# balancewheel.net
KiCad netlist of a schematic drawn in EAGLE
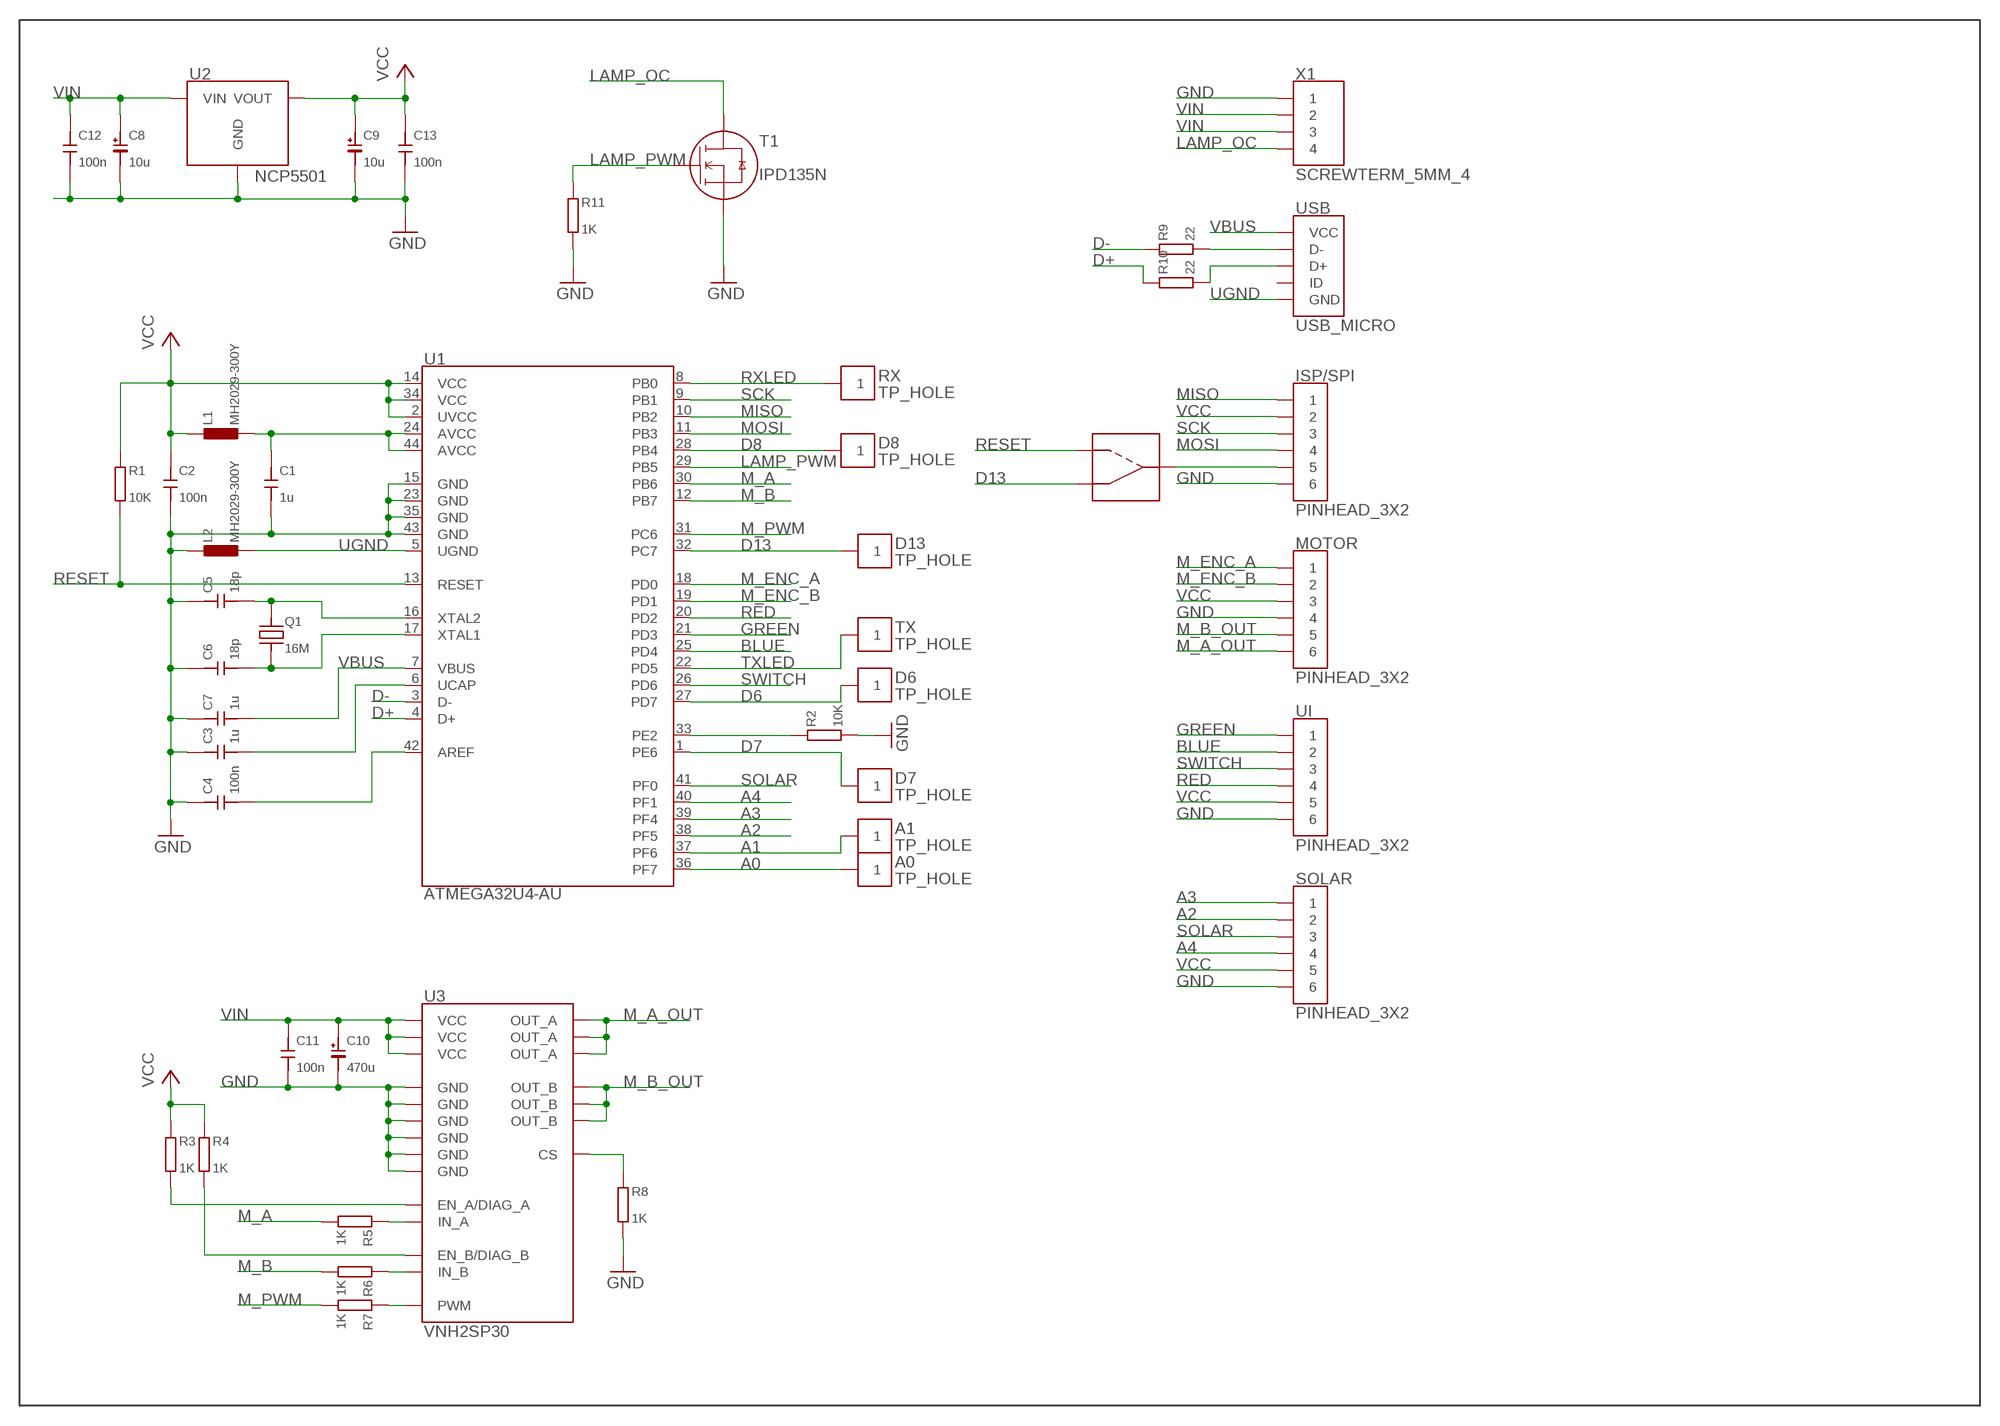
[diagram p0: schematic, sheet 1]

(export (version "E")
  (design (tool "Eeschema 10.0.6"))
  (components
    (comp (ref "A0")
      (value "TP_HOLE")
      (footprint "eagle-import:X1")
      (libsource (lib "eagle-import") (part "TP_HOLE"))
    )
    (comp (ref "A1")
      (value "TP_HOLE")
      (footprint "eagle-import:X1")
      (libsource (lib "eagle-import") (part "TP_HOLE"))
    )
    (comp (ref "C1")
      (value "1u")
      (footprint "eagle-import:0805")
      (libsource (lib "eagle-import") (part "C0805"))
    )
    (comp (ref "C2")
      (value "100n")
      (footprint "eagle-import:0805")
      (libsource (lib "eagle-import") (part "C0805"))
    )
    (comp (ref "C3")
      (value "1u")
      (footprint "eagle-import:0805")
      (libsource (lib "eagle-import") (part "C0805"))
    )
    (comp (ref "C4")
      (value "100n")
      (footprint "eagle-import:0805")
      (libsource (lib "eagle-import") (part "C0805"))
    )
    (comp (ref "C5")
      (value "18p")
      (footprint "eagle-import:0805")
      (libsource (lib "eagle-import") (part "C0805"))
    )
    (comp (ref "C6")
      (value "18p")
      (footprint "eagle-import:0805")
      (libsource (lib "eagle-import") (part "C0805"))
    )
    (comp (ref "C7")
      (value "1u")
      (footprint "eagle-import:0805")
      (libsource (lib "eagle-import") (part "C0805"))
    )
    (comp (ref "C8")
      (value "10u")
      (footprint "eagle-import:CPOL_C")
      (libsource (lib "eagle-import") (part "CPOL_C"))
    )
    (comp (ref "C9")
      (value "10u")
      (footprint "eagle-import:CPOL_C")
      (libsource (lib "eagle-import") (part "CPOL_C"))
    )
    (comp (ref "C10")
      (value "470u")
      (footprint "eagle-import:CPOL_10")
      (libsource (lib "eagle-import") (part "CPOL_10"))
    )
    (comp (ref "C11")
      (value "100n")
      (footprint "eagle-import:0805")
      (libsource (lib "eagle-import") (part "C0805"))
    )
    (comp (ref "C12")
      (value "100n")
      (footprint "eagle-import:0805")
      (libsource (lib "eagle-import") (part "C0805"))
    )
    (comp (ref "C13")
      (value "100n")
      (footprint "eagle-import:0805")
      (libsource (lib "eagle-import") (part "C0805"))
    )
    (comp (ref "D6")
      (value "TP_HOLE")
      (footprint "eagle-import:X1")
      (libsource (lib "eagle-import") (part "TP_HOLE"))
    )
    (comp (ref "D7")
      (value "TP_HOLE")
      (footprint "eagle-import:X1")
      (libsource (lib "eagle-import") (part "TP_HOLE"))
    )
    (comp (ref "D8")
      (value "TP_HOLE")
      (footprint "eagle-import:X1")
      (libsource (lib "eagle-import") (part "TP_HOLE"))
    )
    (comp (ref "D13")
      (value "TP_HOLE")
      (footprint "eagle-import:X1")
      (libsource (lib "eagle-import") (part "TP_HOLE"))
    )
    (comp (ref "ISP/SPI")
      (value "PINHEAD_3X2")
      (footprint "eagle-import:3X2")
      (libsource (lib "eagle-import") (part "PINHEAD_3X2"))
    )
    (comp (ref "L1")
      (value "MH2029-300Y")
      (footprint "eagle-import:0805")
      (libsource (lib "eagle-import") (part "L0805"))
    )
    (comp (ref "L2")
      (value "MH2029-300Y")
      (footprint "eagle-import:0805")
      (libsource (lib "eagle-import") (part "L0805"))
    )
    (comp (ref "MOTOR")
      (value "PINHEAD_3X2")
      (footprint "eagle-import:3X2")
      (libsource (lib "eagle-import") (part "PINHEAD_3X2"))
    )
    (comp (ref "Q1")
      (value "16M")
      (footprint "eagle-import:Q5X32")
      (libsource (lib "eagle-import") (part "Q5X32"))
    )
    (comp (ref "R1")
      (value "10K")
      (footprint "eagle-import:0805")
      (libsource (lib "eagle-import") (part "R0805"))
    )
    (comp (ref "R2")
      (value "10K")
      (footprint "eagle-import:0805")
      (libsource (lib "eagle-import") (part "R0805"))
    )
    (comp (ref "R3")
      (value "1K")
      (footprint "eagle-import:0805")
      (libsource (lib "eagle-import") (part "R0805"))
    )
    (comp (ref "R4")
      (value "1K")
      (footprint "eagle-import:0805")
      (libsource (lib "eagle-import") (part "R0805"))
    )
    (comp (ref "R5")
      (value "1K")
      (footprint "eagle-import:0805")
      (libsource (lib "eagle-import") (part "R0805"))
    )
    (comp (ref "R6")
      (value "1K")
      (footprint "eagle-import:0805")
      (libsource (lib "eagle-import") (part "R0805"))
    )
    (comp (ref "R7")
      (value "1K")
      (footprint "eagle-import:0805")
      (libsource (lib "eagle-import") (part "R0805"))
    )
    (comp (ref "R8")
      (value "1K")
      (footprint "eagle-import:0805")
      (libsource (lib "eagle-import") (part "R0805"))
    )
    (comp (ref "R9")
      (value "22")
      (footprint "eagle-import:0805")
      (libsource (lib "eagle-import") (part "R0805"))
    )
    (comp (ref "R10")
      (value "22")
      (footprint "eagle-import:0805")
      (libsource (lib "eagle-import") (part "R0805"))
    )
    (comp (ref "R11")
      (value "1K")
      (footprint "eagle-import:0805")
      (libsource (lib "eagle-import") (part "R0805"))
    )
    (comp (ref "RX")
      (value "TP_HOLE")
      (footprint "eagle-import:X1")
      (libsource (lib "eagle-import") (part "TP_HOLE"))
    )
    (comp (ref "SJ1") (value "SJ") (footprint "eagle-import:X3") (libsource (lib "eagle-import") (part "SJ")))
    (comp (ref "SOLAR")
      (value "PINHEAD_3X2")
      (footprint "eagle-import:3X2")
      (libsource (lib "eagle-import") (part "PINHEAD_3X2"))
    )
    (comp (ref "T1")
      (value "IPD135N")
      (footprint "eagle-import:DPAK")
      (libsource (lib "eagle-import") (part "MOSFET_N_DPAK"))
    )
    (comp (ref "TX")
      (value "TP_HOLE")
      (footprint "eagle-import:X1")
      (libsource (lib "eagle-import") (part "TP_HOLE"))
    )
    (comp (ref "U1")
      (value "ATMEGA32U4-AU")
      (footprint "eagle-import:TQFP44")
      (libsource (lib "eagle-import") (part "ATMEGA32U4-AU"))
    )
    (comp (ref "U2")
      (value "NCP5501")
      (footprint "eagle-import:DPAK")
      (libsource (lib "eagle-import") (part "NCP5501"))
    )
    (comp (ref "U3")
      (value "VNH2SP30")
      (footprint "eagle-import:MULTIPOWER30")
      (libsource (lib "eagle-import") (part "VNH2SP30"))
    )
    (comp (ref "UI")
      (value "PINHEAD_3X2")
      (footprint "eagle-import:3X2")
      (libsource (lib "eagle-import") (part "PINHEAD_3X2"))
    )
    (comp (ref "USB")
      (value "USB_MICRO")
      (footprint "eagle-import:MUSB")
      (libsource (lib "eagle-import") (part "USB_MICRO"))
    )
    (comp (ref "X1")
      (value "SCREWTERM_5MM_4")
      (footprint "eagle-import:5MMSCREWTERMX4")
      (libsource (lib "eagle-import") (part "SCREWTERM_5MM_4"))
    )
  )
  (nets
    (net (code "1") (name "/A0") (class "Default")
      (node (ref "A0") (pin "P$1") (pinfunction "1_P$1") (pintype "bidirectional"))
      (node (ref "U1") (pin "36") (pinfunction "PF7_36") (pintype "bidirectional"))
    )
    (net (code "2") (name "/A1") (class "Default")
      (node (ref "A1") (pin "P$1") (pinfunction "1_P$1") (pintype "bidirectional"))
      (node (ref "U1") (pin "37") (pinfunction "PF6_37") (pintype "bidirectional"))
    )
    (net (code "3") (name "/A2") (class "Default")
      (node (ref "SOLAR") (pin "2") (pinfunction "2_2") (pintype "bidirectional"))
      (node (ref "U1") (pin "38") (pinfunction "PF5_38") (pintype "bidirectional"))
    )
    (net (code "4") (name "/A3") (class "Default")
      (node (ref "SOLAR") (pin "1") (pinfunction "1_1") (pintype "bidirectional"))
      (node (ref "U1") (pin "39") (pinfunction "PF4_39") (pintype "bidirectional"))
    )
    (net (code "5") (name "/A4") (class "Default")
      (node (ref "SOLAR") (pin "4") (pinfunction "4_4") (pintype "bidirectional"))
      (node (ref "U1") (pin "40") (pinfunction "PF1_40") (pintype "bidirectional"))
    )
    (net (code "6") (name "/BLUE") (class "Default")
      (node (ref "U1") (pin "25") (pinfunction "PD4_25") (pintype "bidirectional"))
      (node (ref "UI") (pin "2") (pinfunction "2_2") (pintype "bidirectional"))
    )
    (net (code "7") (name "/D+") (class "Default")
      (node (ref "R10") (pin "P$2") (pinfunction "P$2_P$2") (pintype "bidirectional"))
      (node (ref "U1") (pin "4") (pinfunction "D+_4") (pintype "bidirectional"))
    )
    (net (code "8") (name "/D-") (class "Default")
      (node (ref "R9") (pin "P$2") (pinfunction "P$2_P$2") (pintype "bidirectional"))
      (node (ref "U1") (pin "3") (pinfunction "D-_3") (pintype "bidirectional"))
    )
    (net (code "9") (name "/D6") (class "Default")
      (node (ref "D6") (pin "P$1") (pinfunction "1_P$1") (pintype "bidirectional"))
      (node (ref "U1") (pin "27") (pinfunction "PD7_27") (pintype "bidirectional"))
    )
    (net (code "10") (name "/D7") (class "Default")
      (node (ref "D7") (pin "P$1") (pinfunction "1_P$1") (pintype "bidirectional"))
      (node (ref "U1") (pin "1") (pinfunction "PE6_1") (pintype "bidirectional"))
    )
    (net (code "11") (name "/D8") (class "Default")
      (node (ref "D8") (pin "P$1") (pinfunction "1_P$1") (pintype "bidirectional"))
      (node (ref "U1") (pin "28") (pinfunction "PB4_28") (pintype "bidirectional"))
    )
    (net (code "12") (name "/D13") (class "Default")
      (node (ref "D13") (pin "P$1") (pinfunction "1_P$1") (pintype "bidirectional"))
      (node (ref "SJ1") (pin "1") (pinfunction "1_1") (pintype "bidirectional"))
      (node (ref "U1") (pin "32") (pinfunction "PC7_32") (pintype "bidirectional"))
    )
    (net (code "13") (name "/GREEN") (class "Default")
      (node (ref "U1") (pin "21") (pinfunction "PD3_21") (pintype "bidirectional"))
      (node (ref "UI") (pin "1") (pinfunction "1_1") (pintype "bidirectional"))
    )
    (net (code "14") (name "/LAMP_OC") (class "Default")
      (node (ref "T1") (pin "TAB") (pinfunction "D_TAB") (pintype "bidirectional"))
      (node (ref "X1") (pin "4") (pinfunction "4_4") (pintype "bidirectional"))
    )
    (net (code "15") (name "/LAMP_PWM") (class "Default")
      (node (ref "R11") (pin "P$2") (pinfunction "P$2_P$2") (pintype "bidirectional"))
      (node (ref "T1") (pin "1") (pinfunction "G_1") (pintype "bidirectional"))
      (node (ref "U1") (pin "29") (pinfunction "PB5_29") (pintype "bidirectional"))
    )
    (net (code "16") (name "/MISO") (class "Default")
      (node (ref "ISP/SPI") (pin "1") (pinfunction "1_1") (pintype "bidirectional"))
      (node (ref "U1") (pin "10") (pinfunction "PB2_10") (pintype "bidirectional"))
    )
    (net (code "17") (name "/MOSI") (class "Default")
      (node (ref "ISP/SPI") (pin "4") (pinfunction "4_4") (pintype "bidirectional"))
      (node (ref "U1") (pin "11") (pinfunction "PB3_11") (pintype "bidirectional"))
    )
    (net (code "18") (name "/M_A") (class "Default")
      (node (ref "R5") (pin "P$1") (pinfunction "P$1_P$1") (pintype "bidirectional"))
      (node (ref "U1") (pin "30") (pinfunction "PB6_30") (pintype "bidirectional"))
    )
    (net (code "19") (name "/M_A_OUT") (class "Default")
      (node (ref "MOTOR") (pin "6") (pinfunction "6_6") (pintype "bidirectional"))
      (node (ref "U3") (pin "P$1") (pinfunction "OUT_A_P$1") (pintype "output"))
      (node (ref "U3") (pin "P$25") (pinfunction "OUT_A_P$25") (pintype "output"))
      (node (ref "U3") (pin "P$30") (pinfunction "OUT_A_P$30") (pintype "output"))
    )
    (net (code "20") (name "/M_B") (class "Default")
      (node (ref "R6") (pin "P$1") (pinfunction "P$1_P$1") (pintype "bidirectional"))
      (node (ref "U1") (pin "12") (pinfunction "PB7_12") (pintype "bidirectional"))
    )
    (net (code "21") (name "/M_B_OUT") (class "Default")
      (node (ref "MOTOR") (pin "5") (pinfunction "5_5") (pintype "bidirectional"))
      (node (ref "U3") (pin "P$15") (pinfunction "OUT_B_P$15") (pintype "output"))
      (node (ref "U3") (pin "P$16") (pinfunction "OUT_B_P$16") (pintype "output"))
      (node (ref "U3") (pin "P$21") (pinfunction "OUT_B_P$21") (pintype "output"))
    )
    (net (code "22") (name "/M_ENC_A") (class "Default")
      (node (ref "MOTOR") (pin "1") (pinfunction "1_1") (pintype "bidirectional"))
      (node (ref "U1") (pin "18") (pinfunction "PD0_18") (pintype "bidirectional"))
    )
    (net (code "23") (name "/M_ENC_B") (class "Default")
      (node (ref "MOTOR") (pin "2") (pinfunction "2_2") (pintype "bidirectional"))
      (node (ref "U1") (pin "19") (pinfunction "PD1_19") (pintype "bidirectional"))
    )
    (net (code "24") (name "/M_PWM") (class "Default")
      (node (ref "R7") (pin "P$1") (pinfunction "P$1_P$1") (pintype "bidirectional"))
      (node (ref "U1") (pin "31") (pinfunction "PC6_31") (pintype "bidirectional"))
    )
    (net (code "25") (name "/RED") (class "Default")
      (node (ref "U1") (pin "20") (pinfunction "PD2_20") (pintype "bidirectional"))
      (node (ref "UI") (pin "4") (pinfunction "4_4") (pintype "bidirectional"))
    )
    (net (code "26") (name "/RESET") (class "Default")
      (node (ref "R1") (pin "P$1") (pinfunction "P$1_P$1") (pintype "bidirectional"))
      (node (ref "SJ1") (pin "3") (pinfunction "3_3") (pintype "bidirectional"))
      (node (ref "U1") (pin "13") (pinfunction "RESET_13") (pintype "bidirectional"))
    )
    (net (code "27") (name "/RXLED") (class "Default")
      (node (ref "RX") (pin "P$1") (pinfunction "1_P$1") (pintype "bidirectional"))
      (node (ref "U1") (pin "8") (pinfunction "PB0_8") (pintype "bidirectional"))
    )
    (net (code "28") (name "/SCK") (class "Default")
      (node (ref "ISP/SPI") (pin "3") (pinfunction "3_3") (pintype "bidirectional"))
      (node (ref "U1") (pin "9") (pinfunction "PB1_9") (pintype "bidirectional"))
    )
    (net (code "29") (name "/SOLAR") (class "Default")
      (node (ref "SOLAR") (pin "3") (pinfunction "3_3") (pintype "bidirectional"))
      (node (ref "U1") (pin "41") (pinfunction "PF0_41") (pintype "bidirectional"))
    )
    (net (code "30") (name "/SWITCH") (class "Default")
      (node (ref "U1") (pin "26") (pinfunction "PD6_26") (pintype "bidirectional"))
      (node (ref "UI") (pin "3") (pinfunction "3_3") (pintype "bidirectional"))
    )
    (net (code "31") (name "/TXLED") (class "Default")
      (node (ref "TX") (pin "P$1") (pinfunction "1_P$1") (pintype "bidirectional"))
      (node (ref "U1") (pin "22") (pinfunction "PD5_22") (pintype "bidirectional"))
    )
    (net (code "32") (name "/UGND") (class "Default")
      (node (ref "L2") (pin "P$1") (pinfunction "P$1_P$1") (pintype "bidirectional"))
      (node (ref "U1") (pin "5") (pinfunction "UGND_5") (pintype "power_in"))
      (node (ref "USB") (pin "5") (pinfunction "GND_5") (pintype "bidirectional"))
    )
    (net (code "33") (name "/VBUS") (class "Default")
      (node (ref "C7") (pin "P$1") (pinfunction "P$1_P$1") (pintype "bidirectional"))
      (node (ref "U1") (pin "7") (pinfunction "VBUS_7") (pintype "bidirectional"))
      (node (ref "USB") (pin "1") (pinfunction "VCC_1") (pintype "bidirectional"))
    )
    (net (code "34") (name "/VIN") (class "Default")
      (node (ref "C10") (pin "POS") (pinfunction "POS_POS") (pintype "bidirectional"))
      (node (ref "C11") (pin "P$2") (pinfunction "P$2_P$2") (pintype "bidirectional"))
      (node (ref "C12") (pin "P$2") (pinfunction "P$2_P$2") (pintype "bidirectional"))
      (node (ref "C8") (pin "POS") (pinfunction "POS_POS") (pintype "bidirectional"))
      (node (ref "U2") (pin "1") (pinfunction "VIN_1") (pintype "power_in"))
      (node (ref "U3") (pin "P$13") (pinfunction "VCC_P$13") (pintype "power_in"))
      (node (ref "U3") (pin "P$23") (pinfunction "VCC_P$23") (pintype "power_in"))
      (node (ref "U3") (pin "P$3") (pinfunction "VCC_P$3") (pintype "power_in"))
      (node (ref "X1") (pin "2") (pinfunction "2_2") (pintype "bidirectional"))
      (node (ref "X1") (pin "3") (pinfunction "3_3") (pintype "bidirectional"))
    )
    (net (code "35") (name "GND") (class "Default")
      (node (ref "C1") (pin "P$1") (pinfunction "P$1_P$1") (pintype "bidirectional"))
      (node (ref "C10") (pin "NEG") (pinfunction "NEG_NEG") (pintype "bidirectional"))
      (node (ref "C11") (pin "P$1") (pinfunction "P$1_P$1") (pintype "bidirectional"))
      (node (ref "C12") (pin "P$1") (pinfunction "P$1_P$1") (pintype "bidirectional"))
      (node (ref "C13") (pin "P$1") (pinfunction "P$1_P$1") (pintype "bidirectional"))
      (node (ref "C2") (pin "P$1") (pinfunction "P$1_P$1") (pintype "bidirectional"))
      (node (ref "C3") (pin "P$2") (pinfunction "P$2_P$2") (pintype "bidirectional"))
      (node (ref "C4") (pin "P$2") (pinfunction "P$2_P$2") (pintype "bidirectional"))
      (node (ref "C5") (pin "P$2") (pinfunction "P$2_P$2") (pintype "bidirectional"))
      (node (ref "C6") (pin "P$2") (pinfunction "P$2_P$2") (pintype "bidirectional"))
      (node (ref "C7") (pin "P$2") (pinfunction "P$2_P$2") (pintype "bidirectional"))
      (node (ref "C8") (pin "NEG") (pinfunction "NEG_NEG") (pintype "bidirectional"))
      (node (ref "C9") (pin "NEG") (pinfunction "NEG_NEG") (pintype "bidirectional"))
      (node (ref "ISP/SPI") (pin "6") (pinfunction "6_6") (pintype "bidirectional"))
      (node (ref "L2") (pin "P$2") (pinfunction "P$2_P$2") (pintype "bidirectional"))
      (node (ref "MOTOR") (pin "4") (pinfunction "4_4") (pintype "bidirectional"))
      (node (ref "R11") (pin "P$1") (pinfunction "P$1_P$1") (pintype "bidirectional"))
      (node (ref "R2") (pin "P$1") (pinfunction "P$1_P$1") (pintype "bidirectional"))
      (node (ref "R8") (pin "P$1") (pinfunction "P$1_P$1") (pintype "bidirectional"))
      (node (ref "SOLAR") (pin "6") (pinfunction "6_6") (pintype "bidirectional"))
      (node (ref "T1") (pin "3") (pinfunction "S_3") (pintype "bidirectional"))
      (node (ref "U1") (pin "15") (pinfunction "GND_15") (pintype "power_in"))
      (node (ref "U1") (pin "23") (pinfunction "GND_23") (pintype "power_in"))
      (node (ref "U1") (pin "35") (pinfunction "GND_35") (pintype "power_in"))
      (node (ref "U1") (pin "43") (pinfunction "GND_43") (pintype "power_in"))
      (node (ref "U2") (pin "TAB") (pinfunction "GND_TAB") (pintype "power_in"))
      (node (ref "U3") (pin "P$18") (pinfunction "GND_P$18") (pintype "power_in"))
      (node (ref "U3") (pin "P$19") (pinfunction "GND_P$19") (pintype "power_in"))
      (node (ref "U3") (pin "P$20") (pinfunction "GND_P$20") (pintype "power_in"))
      (node (ref "U3") (pin "P$26") (pinfunction "GND_P$26") (pintype "power_in"))
      (node (ref "U3") (pin "P$27") (pinfunction "GND_P$27") (pintype "power_in"))
      (node (ref "U3") (pin "P$28") (pinfunction "GND_P$28") (pintype "power_in"))
      (node (ref "UI") (pin "6") (pinfunction "6_6") (pintype "bidirectional"))
      (node (ref "X1") (pin "1") (pinfunction "1_1") (pintype "bidirectional"))
    )
    (net (code "36") (name "Net-(C1-PadP$2)") (class "Default")
      (node (ref "C1") (pin "P$2") (pinfunction "P$2_P$2") (pintype "bidirectional"))
      (node (ref "L1") (pin "P$1") (pinfunction "P$1_P$1") (pintype "bidirectional"))
      (node (ref "U1") (pin "24") (pinfunction "AVCC_24") (pintype "power_in"))
      (node (ref "U1") (pin "44") (pinfunction "AVCC_44") (pintype "power_in"))
    )
    (net (code "37") (name "Net-(ISP/SPI-Pad5)") (class "Default")
      (node (ref "ISP/SPI") (pin "5") (pinfunction "5_5") (pintype "bidirectional"))
      (node (ref "SJ1") (pin "2") (pinfunction "2_2") (pintype "bidirectional"))
    )
    (net (code "38") (name "Net-(U1-AREF)") (class "Default")
      (node (ref "C4") (pin "P$1") (pinfunction "P$1_P$1") (pintype "bidirectional"))
      (node (ref "U1") (pin "42") (pinfunction "AREF_42") (pintype "bidirectional"))
    )
    (net (code "39") (name "Net-(U1-PE2)") (class "Default")
      (node (ref "R2") (pin "P$2") (pinfunction "P$2_P$2") (pintype "bidirectional"))
      (node (ref "U1") (pin "33") (pinfunction "PE2_33") (pintype "bidirectional"))
    )
    (net (code "40") (name "Net-(U1-UCAP)") (class "Default")
      (node (ref "C3") (pin "P$1") (pinfunction "P$1_P$1") (pintype "bidirectional"))
      (node (ref "U1") (pin "6") (pinfunction "UCAP_6") (pintype "bidirectional"))
    )
    (net (code "41") (name "Net-(U1-XTAL1)") (class "Default")
      (node (ref "C6") (pin "P$1") (pinfunction "P$1_P$1") (pintype "bidirectional"))
      (node (ref "Q1") (pin "P$1") (pinfunction "P$1_P$1") (pintype "bidirectional"))
      (node (ref "U1") (pin "17") (pinfunction "XTAL1_17") (pintype "bidirectional"))
    )
    (net (code "42") (name "Net-(U1-XTAL2)") (class "Default")
      (node (ref "C5") (pin "P$1") (pinfunction "P$1_P$1") (pintype "bidirectional"))
      (node (ref "Q1") (pin "P$2") (pinfunction "P$2_P$2") (pintype "bidirectional"))
      (node (ref "U1") (pin "16") (pinfunction "XTAL2_16") (pintype "bidirectional"))
    )
    (net (code "43") (name "Net-(U3-CS)") (class "Default")
      (node (ref "R8") (pin "P$2") (pinfunction "P$2_P$2") (pintype "bidirectional"))
      (node (ref "U3") (pin "P$9") (pinfunction "CS_P$9") (pintype "output"))
    )
    (net (code "44") (name "Net-(U3-EN_A{slash}DIAG_A)") (class "Default")
      (node (ref "R3") (pin "P$1") (pinfunction "P$1_P$1") (pintype "bidirectional"))
      (node (ref "U3") (pin "P$6") (pinfunction "EN_A/DIAG_A_P$6") (pintype "bidirectional"))
    )
    (net (code "45") (name "Net-(U3-EN_B{slash}DIAG_B)") (class "Default")
      (node (ref "R4") (pin "P$1") (pinfunction "P$1_P$1") (pintype "bidirectional"))
      (node (ref "U3") (pin "P$10") (pinfunction "EN_B/DIAG_B_P$10") (pintype "bidirectional"))
    )
    (net (code "46") (name "Net-(U3-IN_A)") (class "Default")
      (node (ref "R5") (pin "P$2") (pinfunction "P$2_P$2") (pintype "bidirectional"))
      (node (ref "U3") (pin "P$5") (pinfunction "IN_A_P$5") (pintype "input"))
    )
    (net (code "47") (name "Net-(U3-IN_B)") (class "Default")
      (node (ref "R6") (pin "P$2") (pinfunction "P$2_P$2") (pintype "bidirectional"))
      (node (ref "U3") (pin "P$11") (pinfunction "IN_B_P$11") (pintype "input"))
    )
    (net (code "48") (name "Net-(U3-PWM)") (class "Default")
      (node (ref "R7") (pin "P$2") (pinfunction "P$2_P$2") (pintype "bidirectional"))
      (node (ref "U3") (pin "P$8") (pinfunction "PWM_P$8") (pintype "input"))
    )
    (net (code "49") (name "Net-(USB-D+)") (class "Default")
      (node (ref "R10") (pin "P$1") (pinfunction "P$1_P$1") (pintype "bidirectional"))
      (node (ref "USB") (pin "3") (pinfunction "D+_3") (pintype "bidirectional"))
    )
    (net (code "50") (name "Net-(USB-D-)") (class "Default")
      (node (ref "R9") (pin "P$1") (pinfunction "P$1_P$1") (pintype "bidirectional"))
      (node (ref "USB") (pin "2") (pinfunction "D-_2") (pintype "bidirectional"))
    )
    (net (code "51") (name "VCC") (class "Default")
      (node (ref "C13") (pin "P$2") (pinfunction "P$2_P$2") (pintype "bidirectional"))
      (node (ref "C2") (pin "P$2") (pinfunction "P$2_P$2") (pintype "bidirectional"))
      (node (ref "C9") (pin "POS") (pinfunction "POS_POS") (pintype "bidirectional"))
      (node (ref "ISP/SPI") (pin "2") (pinfunction "2_2") (pintype "bidirectional"))
      (node (ref "L1") (pin "P$2") (pinfunction "P$2_P$2") (pintype "bidirectional"))
      (node (ref "MOTOR") (pin "3") (pinfunction "3_3") (pintype "bidirectional"))
      (node (ref "R1") (pin "P$2") (pinfunction "P$2_P$2") (pintype "bidirectional"))
      (node (ref "R3") (pin "P$2") (pinfunction "P$2_P$2") (pintype "bidirectional"))
      (node (ref "R4") (pin "P$2") (pinfunction "P$2_P$2") (pintype "bidirectional"))
      (node (ref "SOLAR") (pin "5") (pinfunction "5_5") (pintype "bidirectional"))
      (node (ref "U1") (pin "14") (pinfunction "VCC_14") (pintype "power_in"))
      (node (ref "U1") (pin "2") (pinfunction "UVCC_2") (pintype "power_in"))
      (node (ref "U1") (pin "34") (pinfunction "VCC_34") (pintype "power_in"))
      (node (ref "U2") (pin "3") (pinfunction "VOUT_3") (pintype "power_in"))
      (node (ref "UI") (pin "5") (pinfunction "5_5") (pintype "bidirectional"))
    )
    (net (code "52") (name "unconnected-(USB-ID-Pad4)") (class "Default")
      (node (ref "USB") (pin "4") (pinfunction "ID_4") (pintype "bidirectional"))
    )
  )
)
